# primary_DIO.net
KiCad netlist of a schematic drawn in Altium Designer
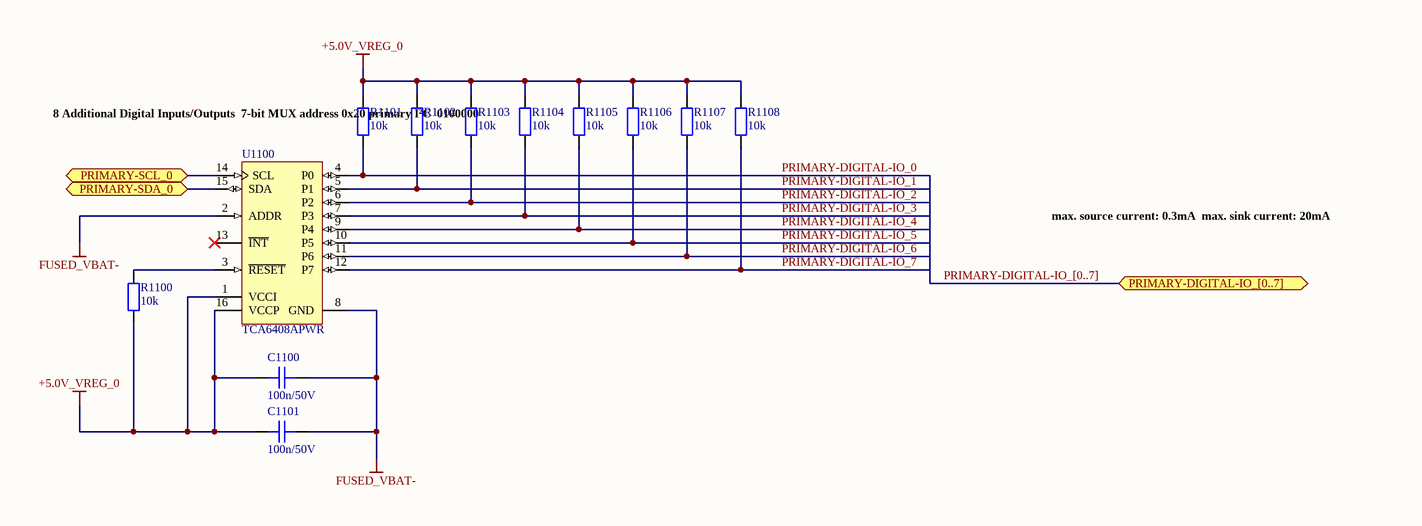
[diagram p0: primary_DIO.SchDoc]

(export (version "E")
  (design (tool "Eeschema 10.0.6"))
  (components
    (comp (ref "C1100")
      (value "100n/50V")
      (footprint "CAPC1608X08N")
      (description "MLCC")
      (fields (field (name "PART NUMBER") "gen_C_ceramic_100n_50V_X7R_0603"))
      (libsource (lib "OE750") (part "C"))
    )
    (comp (ref "C1101")
      (value "100n/50V")
      (footprint "CAPC1608X08N")
      (description "MLCC")
      (fields (field (name "PART NUMBER") "gen_C_ceramic_100n_50V_X7R_0603"))
      (libsource (lib "OE750") (part "C"))
    )
    (comp (ref "R1100")
      (value "10k")
      (footprint "RESC1608X05N")
      (description "SMD Resistor 10k 0603")
      (fields (field (name "PART NUMBER") "gen_R_10k_0603") (field (name "TOLERANCE") "1%"))
      (libsource (lib "OE750") (part "R"))
    )
    (comp (ref "R1101")
      (value "10k")
      (footprint "RESC1608X05N")
      (description "SMD Resistor 10k 0603")
      (fields (field (name "PART NUMBER") "gen_R_10k_0603") (field (name "TOLERANCE") "1%"))
      (libsource (lib "OE750") (part "R"))
    )
    (comp (ref "R1102")
      (value "10k")
      (footprint "RESC1608X05N")
      (description "SMD Resistor 10k 0603")
      (fields (field (name "PART NUMBER") "gen_R_10k_0603") (field (name "TOLERANCE") "1%"))
      (libsource (lib "OE750") (part "R"))
    )
    (comp (ref "R1103")
      (value "10k")
      (footprint "RESC1608X05N")
      (description "SMD Resistor 10k 0603")
      (fields (field (name "PART NUMBER") "gen_R_10k_0603") (field (name "TOLERANCE") "1%"))
      (libsource (lib "OE750") (part "R"))
    )
    (comp (ref "R1104")
      (value "10k")
      (footprint "RESC1608X05N")
      (description "SMD Resistor 10k 0603")
      (fields (field (name "PART NUMBER") "gen_R_10k_0603") (field (name "TOLERANCE") "1%"))
      (libsource (lib "OE750") (part "R"))
    )
    (comp (ref "R1105")
      (value "10k")
      (footprint "RESC1608X05N")
      (description "SMD Resistor 10k 0603")
      (fields (field (name "PART NUMBER") "gen_R_10k_0603") (field (name "TOLERANCE") "1%"))
      (libsource (lib "OE750") (part "R"))
    )
    (comp (ref "R1106")
      (value "10k")
      (footprint "RESC1608X05N")
      (description "SMD Resistor 10k 0603")
      (fields (field (name "PART NUMBER") "gen_R_10k_0603") (field (name "TOLERANCE") "1%"))
      (libsource (lib "OE750") (part "R"))
    )
    (comp (ref "R1107")
      (value "10k")
      (footprint "RESC1608X05N")
      (description "SMD Resistor 10k 0603")
      (fields (field (name "PART NUMBER") "gen_R_10k_0603") (field (name "TOLERANCE") "1%"))
      (libsource (lib "OE750") (part "R"))
    )
    (comp (ref "R1108")
      (value "10k")
      (footprint "RESC1608X05N")
      (description "SMD Resistor 10k 0603")
      (fields (field (name "PART NUMBER") "gen_R_10k_0603") (field (name "TOLERANCE") "1%"))
      (libsource (lib "OE750") (part "R"))
    )
    (comp (ref "U1100")
      (value "TCA6408APWR")
      (footprint "PW0016A_L")
      (fields (field (name "MANUFACTURER") "Texas Instruments"))
      (libsource (lib "Altium Content Vault") (part "TI-TCA6408A-TSSOP_PW-16"))
    )
  )
  (nets
    (net (code "1") (name "+5.0V_VREG_0") (class "Default")
      (node (ref "C1100") (pin "2") (pinfunction "2_2") (pintype "passive"))
      (node (ref "C1101") (pin "2") (pinfunction "2_2") (pintype "passive"))
      (node (ref "R1100") (pin "1") (pinfunction "1_1") (pintype "passive"))
      (node (ref "R1101") (pin "2") (pinfunction "2_2") (pintype "passive"))
      (node (ref "R1102") (pin "2") (pinfunction "2_2") (pintype "passive"))
      (node (ref "R1103") (pin "2") (pinfunction "2_2") (pintype "passive"))
      (node (ref "R1104") (pin "2") (pinfunction "2_2") (pintype "passive"))
      (node (ref "R1105") (pin "2") (pinfunction "2_2") (pintype "passive"))
      (node (ref "R1106") (pin "2") (pinfunction "2_2") (pintype "passive"))
      (node (ref "R1107") (pin "2") (pinfunction "2_2") (pintype "passive"))
      (node (ref "R1108") (pin "2") (pinfunction "2_2") (pintype "passive"))
      (node (ref "U1100") (pin "1") (pinfunction "VCCI_1") (pintype "power_in"))
      (node (ref "U1100") (pin "16") (pinfunction "VCCP_16") (pintype "power_in"))
    )
    (net (code "2") (name "/PRIMARY-DIGITAL-IO_0") (class "Default")
      (node (ref "R1101") (pin "1") (pinfunction "1_1") (pintype "passive"))
      (node (ref "U1100") (pin "4") (pinfunction "P0_4") (pintype "bidirectional"))
    )
    (net (code "3") (name "/PRIMARY-DIGITAL-IO_1") (class "Default")
      (node (ref "R1102") (pin "1") (pinfunction "1_1") (pintype "passive"))
      (node (ref "U1100") (pin "5") (pinfunction "P1_5") (pintype "bidirectional"))
    )
    (net (code "4") (name "/PRIMARY-DIGITAL-IO_2") (class "Default")
      (node (ref "R1103") (pin "1") (pinfunction "1_1") (pintype "passive"))
      (node (ref "U1100") (pin "6") (pinfunction "P2_6") (pintype "bidirectional"))
    )
    (net (code "5") (name "/PRIMARY-DIGITAL-IO_3") (class "Default")
      (node (ref "R1104") (pin "1") (pinfunction "1_1") (pintype "passive"))
      (node (ref "U1100") (pin "7") (pinfunction "P3_7") (pintype "bidirectional"))
    )
    (net (code "6") (name "/PRIMARY-DIGITAL-IO_4") (class "Default")
      (node (ref "R1105") (pin "1") (pinfunction "1_1") (pintype "passive"))
      (node (ref "U1100") (pin "9") (pinfunction "P4_9") (pintype "bidirectional"))
    )
    (net (code "7") (name "/PRIMARY-DIGITAL-IO_5") (class "Default")
      (node (ref "R1106") (pin "1") (pinfunction "1_1") (pintype "passive"))
      (node (ref "U1100") (pin "10") (pinfunction "P5_10") (pintype "bidirectional"))
    )
    (net (code "8") (name "/PRIMARY-DIGITAL-IO_6") (class "Default")
      (node (ref "R1107") (pin "1") (pinfunction "1_1") (pintype "passive"))
      (node (ref "U1100") (pin "11") (pinfunction "P6_11") (pintype "bidirectional"))
    )
    (net (code "9") (name "/PRIMARY-DIGITAL-IO_7") (class "Default")
      (node (ref "R1108") (pin "1") (pinfunction "1_1") (pintype "passive"))
      (node (ref "U1100") (pin "12") (pinfunction "P7_12") (pintype "bidirectional"))
    )
    (net (code "11") (name "/PRIMARY-SCL_0") (class "Default")
      (node (ref "U1100") (pin "14") (pinfunction "SCL_14") (pintype "input"))
    )
    (net (code "12") (name "/PRIMARY-SDA_0") (class "Default")
      (node (ref "U1100") (pin "15") (pinfunction "SDA_15") (pintype "bidirectional"))
    )
    (net (code "13") (name "FUSED_VBAT-") (class "Default")
      (node (ref "C1100") (pin "1") (pinfunction "1_1") (pintype "passive"))
      (node (ref "C1101") (pin "1") (pinfunction "1_1") (pintype "passive"))
      (node (ref "U1100") (pin "2") (pinfunction "ADDR_2") (pintype "input"))
      (node (ref "U1100") (pin "8") (pinfunction "GND_8") (pintype "power_in"))
    )
    (net (code "14") (name "Net-(U1100-~{RESET})") (class "Default")
      (node (ref "R1100") (pin "2") (pinfunction "2_2") (pintype "passive"))
      (node (ref "U1100") (pin "3") (pinfunction "~{RESET}_3") (pintype "input"))
    )
    (net (code "15") (name "unconnected-(U1100-~{INT}-Pad13)") (class "Default")
      (node (ref "U1100") (pin "13") (pinfunction "~{INT}_13") (pintype "open_collector+no_connect"))
    )
  )
)
